# epnet.net
KiCad netlist of a schematic drawn in EAGLE
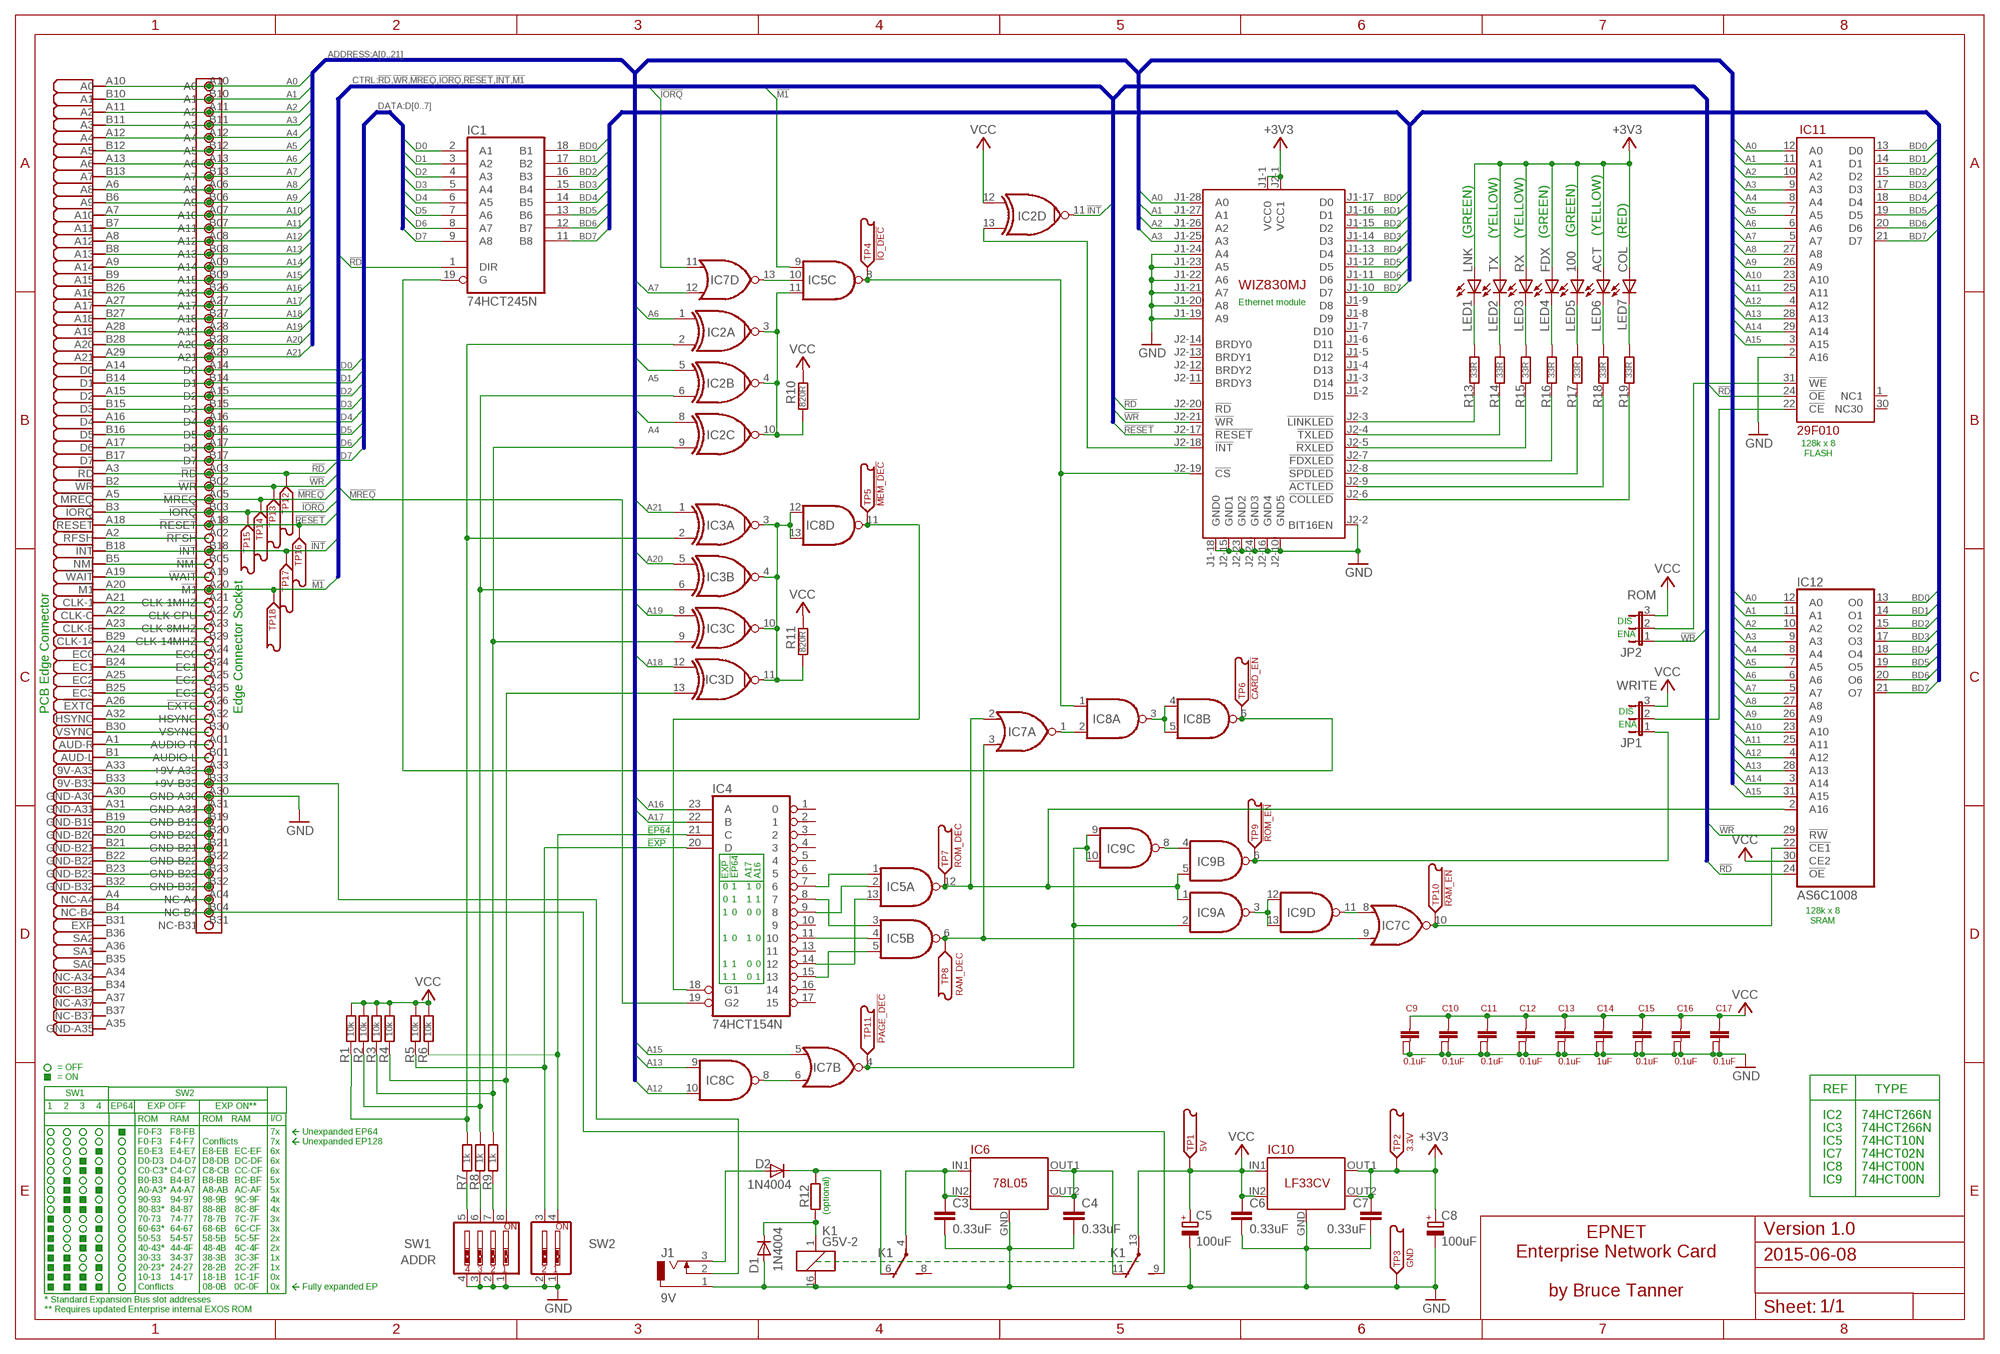
[diagram p0: schematic, sheet 1]

(export (version "E")
  (design (tool "Eeschema 10.0.6"))
  (components
    (comp (ref "C1")
      (value "Edge Connector")
      (footprint "eagle-import:CON-EDGE")
      (libsource (lib "eagle-import") (part "CON-EDGE"))
    )
    (comp (ref "C2")
      (value "CON-EXPANSION")
      (footprint "eagle-import:EXPSOCKET")
      (libsource (lib "eagle-import") (part "CON-EXPANSION"))
    )
    (comp (ref "C3")
      (value "0.33uF")
      (footprint "eagle-import:C050-025X075")
      (libsource (lib "eagle-import") (part "C-EU050-025X075"))
    )
    (comp (ref "C4")
      (value "0.33uF")
      (footprint "eagle-import:C050-025X075")
      (libsource (lib "eagle-import") (part "C-EU050-025X075"))
    )
    (comp (ref "C5")
      (value "100uF")
      (footprint "eagle-import:E2,5-7")
      (libsource (lib "eagle-import") (part "CPOL-EUE2.5-7"))
    )
    (comp (ref "C6")
      (value "0.33uF")
      (footprint "eagle-import:C050-025X075")
      (libsource (lib "eagle-import") (part "C-EU050-025X075"))
    )
    (comp (ref "C7")
      (value "0.33uF")
      (footprint "eagle-import:C050-025X075")
      (libsource (lib "eagle-import") (part "C-EU050-025X075"))
    )
    (comp (ref "C8")
      (value "100uF")
      (footprint "eagle-import:E2,5-7")
      (libsource (lib "eagle-import") (part "CPOL-EUE2.5-7"))
    )
    (comp (ref "C9")
      (value "0.1uF")
      (footprint "eagle-import:CAPACITOR")
      (libsource (lib "eagle-import") (part "CAPACITOR"))
    )
    (comp (ref "C10")
      (value "0.1uF")
      (footprint "eagle-import:CAPACITOR")
      (libsource (lib "eagle-import") (part "CAPACITOR"))
    )
    (comp (ref "C11")
      (value "0.1uF")
      (footprint "eagle-import:CAPACITOR")
      (libsource (lib "eagle-import") (part "CAPACITOR"))
    )
    (comp (ref "C12")
      (value "0.1uF")
      (footprint "eagle-import:CAPACITOR")
      (libsource (lib "eagle-import") (part "CAPACITOR"))
    )
    (comp (ref "C13")
      (value "0.1uF")
      (footprint "eagle-import:CAPACITOR")
      (libsource (lib "eagle-import") (part "CAPACITOR"))
    )
    (comp (ref "C14")
      (value "1uF")
      (footprint "eagle-import:CAPACITOR")
      (libsource (lib "eagle-import") (part "CAPACITOR"))
    )
    (comp (ref "C15")
      (value "0.1uF")
      (footprint "eagle-import:CAPACITOR")
      (libsource (lib "eagle-import") (part "CAPACITOR"))
    )
    (comp (ref "C16")
      (value "0.1uF")
      (footprint "eagle-import:CAPACITOR")
      (libsource (lib "eagle-import") (part "CAPACITOR"))
    )
    (comp (ref "C17")
      (value "0.1uF")
      (footprint "eagle-import:CAPACITOR")
      (libsource (lib "eagle-import") (part "CAPACITOR"))
    )
    (comp (ref "D1")
      (value "1N4004")
      (footprint "eagle-import:DO41-10")
      (libsource (lib "eagle-import") (part "1N4004"))
    )
    (comp (ref "D2")
      (value "1N4004")
      (footprint "eagle-import:DO41-10")
      (libsource (lib "eagle-import") (part "1N4004"))
    )
    (comp (ref "IC1")
      (value "74HCT245N")
      (footprint "eagle-import:DIL20")
      (libsource (lib "eagle-import") (part "74245NLS"))
    )
    (comp (ref "IC2")
      (value "74LS266N")
      (footprint "eagle-import:DIL14")
      (libsource (lib "eagle-import") (part "74266NLS"))
    )
    (comp (ref "IC3")
      (value "74LS266N")
      (footprint "eagle-import:DIL14")
      (libsource (lib "eagle-import") (part "74266NLS"))
    )
    (comp (ref "IC4")
      (value "74HCT154N")
      (footprint "eagle-import:DIL24-6")
      (libsource (lib "eagle-import") (part "74154N"))
    )
    (comp (ref "IC5")
      (value "74AS10N")
      (footprint "eagle-import:DIL14")
      (libsource (lib "eagle-import") (part "7410NAS"))
    )
    (comp (ref "IC6")
      (value "78L05")
      (footprint "eagle-import:REGULATOR")
      (libsource (lib "eagle-import") (part "REGULATOR"))
    )
    (comp (ref "IC7")
      (value "74LS02N")
      (footprint "eagle-import:DIL14")
      (libsource (lib "eagle-import") (part "7402NLS"))
    )
    (comp (ref "IC8")
      (value "74LS00N")
      (footprint "eagle-import:DIL14")
      (libsource (lib "eagle-import") (part "7400NLS"))
    )
    (comp (ref "IC9")
      (value "74LS00N")
      (footprint "eagle-import:DIL14")
      (libsource (lib "eagle-import") (part "7400NLS"))
    )
    (comp (ref "IC10")
      (value "LF33CV")
      (footprint "eagle-import:REGULATOR")
      (libsource (lib "eagle-import") (part "REGULATOR"))
    )
    (comp (ref "IC11")
      (value "29F010")
      (footprint "eagle-import:20F010")
      (libsource (lib "eagle-import") (part "29F010"))
    )
    (comp (ref "IC12")
      (value "AS6C1008")
      (footprint "eagle-import:DIL32")
      (libsource (lib "eagle-import") (part "TC551001CP"))
    )
    (comp (ref "J1")
      (value "9V")
      (footprint "eagle-import:DCJ0202")
      (libsource (lib "eagle-import") (part "DCJ0202"))
    )
    (comp (ref "JP1")
      (value "WRITE")
      (footprint "eagle-import:JP2")
      (libsource (lib "eagle-import") (part "JP2E"))
    )
    (comp (ref "JP2")
      (value "ROM")
      (footprint "eagle-import:JP2")
      (libsource (lib "eagle-import") (part "JP2E"))
    )
    (comp (ref "K1")
      (value "G5V-2")
      (footprint "eagle-import:G5V-2")
      (fields (field (name "MPN") "G5V-2 5DC"))
      (libsource (lib "eagle-import") (part "G5V-2"))
    )
    (comp (ref "LED1")
      (value "LNK")
      (footprint "eagle-import:LED3MM")
      (libsource (lib "eagle-import") (part "LED3MM"))
    )
    (comp (ref "LED2")
      (value "TX")
      (footprint "eagle-import:LED3MM")
      (libsource (lib "eagle-import") (part "LED3MM"))
    )
    (comp (ref "LED3")
      (value "RX")
      (footprint "eagle-import:LED3MM")
      (libsource (lib "eagle-import") (part "LED3MM"))
    )
    (comp (ref "LED4")
      (value "FDX")
      (footprint "eagle-import:LED3MM")
      (libsource (lib "eagle-import") (part "LED3MM"))
    )
    (comp (ref "LED5")
      (value "100")
      (footprint "eagle-import:LED3MM")
      (libsource (lib "eagle-import") (part "LED3MM"))
    )
    (comp (ref "LED6")
      (value "ACT")
      (footprint "eagle-import:LED3MM")
      (libsource (lib "eagle-import") (part "LED3MM"))
    )
    (comp (ref "LED7")
      (value "COL")
      (footprint "eagle-import:LED3MM")
      (libsource (lib "eagle-import") (part "LED3MM"))
    )
    (comp (ref "M1")
      (value "WIZ830MJ")
      (footprint "eagle-import:WIZ830MJ")
      (libsource (lib "eagle-import") (part "WIZ830MJ"))
    )
    (comp (ref "R1")
      (value "10k")
      (footprint "eagle-import:0309_10")
      (libsource (lib "eagle-import") (part "R-EU_0309/10"))
    )
    (comp (ref "R2")
      (value "10k")
      (footprint "eagle-import:0309_10")
      (libsource (lib "eagle-import") (part "R-EU_0309/10"))
    )
    (comp (ref "R3")
      (value "10k")
      (footprint "eagle-import:0309_10")
      (libsource (lib "eagle-import") (part "R-EU_0309/10"))
    )
    (comp (ref "R4")
      (value "10k")
      (footprint "eagle-import:0309_10")
      (libsource (lib "eagle-import") (part "R-EU_0309/10"))
    )
    (comp (ref "R5")
      (value "10k")
      (footprint "eagle-import:0309_10")
      (libsource (lib "eagle-import") (part "R-EU_0309/10"))
    )
    (comp (ref "R6")
      (value "10k")
      (footprint "eagle-import:0309_10")
      (libsource (lib "eagle-import") (part "R-EU_0309/10"))
    )
    (comp (ref "R7")
      (value "1k")
      (footprint "eagle-import:0309_10")
      (libsource (lib "eagle-import") (part "R-EU_0309/10"))
    )
    (comp (ref "R8")
      (value "1k")
      (footprint "eagle-import:0309_10")
      (libsource (lib "eagle-import") (part "R-EU_0309/10"))
    )
    (comp (ref "R9")
      (value "1k")
      (footprint "eagle-import:0309_10")
      (libsource (lib "eagle-import") (part "R-EU_0309/10"))
    )
    (comp (ref "R10")
      (value "820R")
      (footprint "eagle-import:0309_10")
      (libsource (lib "eagle-import") (part "R-EU_0309/10"))
    )
    (comp (ref "R11")
      (value "820R")
      (footprint "eagle-import:0309_10")
      (libsource (lib "eagle-import") (part "R-EU_0309/10"))
    )
    (comp (ref "R12")
      (value "R-EU_0309/10")
      (footprint "eagle-import:0309_10")
      (libsource (lib "eagle-import") (part "R-EU_0309/10"))
    )
    (comp (ref "R13")
      (value "33R")
      (footprint "eagle-import:0309_10")
      (libsource (lib "eagle-import") (part "R-EU_0309/10"))
    )
    (comp (ref "R14")
      (value "33R")
      (footprint "eagle-import:0309_10")
      (libsource (lib "eagle-import") (part "R-EU_0309/10"))
    )
    (comp (ref "R15")
      (value "33R")
      (footprint "eagle-import:0309_10")
      (libsource (lib "eagle-import") (part "R-EU_0309/10"))
    )
    (comp (ref "R16")
      (value "33R")
      (footprint "eagle-import:0309_10")
      (libsource (lib "eagle-import") (part "R-EU_0309/10"))
    )
    (comp (ref "R17")
      (value "33R")
      (footprint "eagle-import:0309_10")
      (libsource (lib "eagle-import") (part "R-EU_0309/10"))
    )
    (comp (ref "R18")
      (value "33R")
      (footprint "eagle-import:0309_10")
      (libsource (lib "eagle-import") (part "R-EU_0309/10"))
    )
    (comp (ref "R19")
      (value "33R")
      (footprint "eagle-import:0309_10")
      (libsource (lib "eagle-import") (part "R-EU_0309/10"))
    )
    (comp (ref "SW1")
      (value "ADDR")
      (footprint "eagle-import:EDG-04")
      (libsource (lib "eagle-import") (part "SW_DIP-4"))
    )
    (comp (ref "SW2")
      (value "SW_DIP-2")
      (footprint "eagle-import:EDG-02")
      (libsource (lib "eagle-import") (part "SW_DIP-2"))
    )
    (comp (ref "TP1")
      (value "5V")
      (footprint "eagle-import:TESTPOINT")
      (libsource (lib "eagle-import") (part "TESTPOINT"))
    )
    (comp (ref "TP2")
      (value "3.3V")
      (footprint "eagle-import:TESTPOINT")
      (libsource (lib "eagle-import") (part "TESTPOINT"))
    )
    (comp (ref "TP3")
      (value "GND")
      (footprint "eagle-import:TESTPOINT")
      (libsource (lib "eagle-import") (part "TESTPOINT"))
    )
    (comp (ref "TP4")
      (value "!IO_DEC")
      (footprint "eagle-import:TESTPOINT")
      (libsource (lib "eagle-import") (part "TESTPOINT"))
    )
    (comp (ref "TP5")
      (value "!MEM_DEC")
      (footprint "eagle-import:TESTPOINT")
      (libsource (lib "eagle-import") (part "TESTPOINT"))
    )
    (comp (ref "TP6")
      (value "!CARD_EN")
      (footprint "eagle-import:TESTPOINT")
      (libsource (lib "eagle-import") (part "TESTPOINT"))
    )
    (comp (ref "TP7")
      (value "ROM_DEC")
      (footprint "eagle-import:TESTPOINT")
      (libsource (lib "eagle-import") (part "TESTPOINT"))
    )
    (comp (ref "TP8")
      (value "RAM_DEC")
      (footprint "eagle-import:TESTPOINT")
      (libsource (lib "eagle-import") (part "TESTPOINT"))
    )
    (comp (ref "TP9")
      (value "!ROM_EN")
      (footprint "eagle-import:TESTPOINT")
      (libsource (lib "eagle-import") (part "TESTPOINT"))
    )
    (comp (ref "TP10")
      (value "!RAM_EN")
      (footprint "eagle-import:TESTPOINT")
      (libsource (lib "eagle-import") (part "TESTPOINT"))
    )
    (comp (ref "TP11")
      (value "!PAGE_DEC")
      (footprint "eagle-import:TESTPOINT")
      (libsource (lib "eagle-import") (part "TESTPOINT"))
    )
    (comp (ref "TP12")
      (value "!RD")
      (footprint "eagle-import:TESTPOINT")
      (libsource (lib "eagle-import") (part "TESTPOINT"))
    )
    (comp (ref "TP13")
      (value "!WR")
      (footprint "eagle-import:TESTPOINT")
      (libsource (lib "eagle-import") (part "TESTPOINT"))
    )
    (comp (ref "TP14")
      (value "!MREQ")
      (footprint "eagle-import:TESTPOINT")
      (libsource (lib "eagle-import") (part "TESTPOINT"))
    )
    (comp (ref "TP15")
      (value "!IORQ")
      (footprint "eagle-import:TESTPOINT")
      (libsource (lib "eagle-import") (part "TESTPOINT"))
    )
    (comp (ref "TP16")
      (value "!RESET")
      (footprint "eagle-import:TESTPOINT")
      (libsource (lib "eagle-import") (part "TESTPOINT"))
    )
    (comp (ref "TP17")
      (value "!INT")
      (footprint "eagle-import:TESTPOINT")
      (libsource (lib "eagle-import") (part "TESTPOINT"))
    )
    (comp (ref "TP18")
      (value "!M1")
      (footprint "eagle-import:TESTPOINT")
      (libsource (lib "eagle-import") (part "TESTPOINT"))
    )
  )
  (nets
    (net (code "32") (name "+3V3") (class "Default")
      (node (ref "C7") (pin "1") (pinfunction "1_1") (pintype "passive"))
      (node (ref "C8") (pin "+") (pinfunction "+_+") (pintype "passive"))
      (node (ref "IC10") (pin "OUT1") (pinfunction "OUT1_OUT1") (pintype "power_in"))
      (node (ref "IC10") (pin "OUT2") (pinfunction "OUT2_OUT2") (pintype "power_in"))
      (node (ref "LED1") (pin "A") (pinfunction "A_A") (pintype "passive"))
      (node (ref "LED2") (pin "A") (pinfunction "A_A") (pintype "passive"))
      (node (ref "LED3") (pin "A") (pinfunction "A_A") (pintype "passive"))
      (node (ref "LED4") (pin "A") (pinfunction "A_A") (pintype "passive"))
      (node (ref "LED5") (pin "A") (pinfunction "A_A") (pintype "passive"))
      (node (ref "LED6") (pin "A") (pinfunction "A_A") (pintype "passive"))
      (node (ref "LED7") (pin "A") (pinfunction "A_A") (pintype "passive"))
      (node (ref "M1") (pin "J1-1") (pinfunction "VCC0_J1-1") (pintype "input"))
      (node (ref "M1") (pin "J2-1") (pinfunction "VCC1_J2-1") (pintype "input"))
      (node (ref "TP2") (pin "P$1") (pinfunction "TESTPOINT_P$1") (pintype "input"))
    )
    (net (code "33") (name "/A0") (class "Default")
      (node (ref "C1") (pin "A10") (pinfunction "A0_A10") (pintype "output"))
      (node (ref "C2") (pin "A10") (pinfunction "A0_A10") (pintype "input"))
      (node (ref "IC11") (pin "12") (pinfunction "A0_12") (pintype "input"))
      (node (ref "IC12") (pin "12") (pinfunction "A0_12") (pintype "input"))
      (node (ref "M1") (pin "J1-28") (pinfunction "A0_J1-28") (pintype "input"))
    )
    (net (code "34") (name "/A1") (class "Default")
      (node (ref "C1") (pin "B10") (pinfunction "A1_B10") (pintype "output"))
      (node (ref "C2") (pin "B10") (pinfunction "A1_B10") (pintype "input"))
      (node (ref "IC11") (pin "11") (pinfunction "A1_11") (pintype "input"))
      (node (ref "IC12") (pin "11") (pinfunction "A1_11") (pintype "input"))
      (node (ref "M1") (pin "J1-27") (pinfunction "A1_J1-27") (pintype "input"))
    )
    (net (code "35") (name "/A2") (class "Default")
      (node (ref "C1") (pin "A11") (pinfunction "A2_A11") (pintype "output"))
      (node (ref "C2") (pin "A11") (pinfunction "A2_A11") (pintype "input"))
      (node (ref "IC11") (pin "10") (pinfunction "A2_10") (pintype "input"))
      (node (ref "IC12") (pin "10") (pinfunction "A2_10") (pintype "input"))
      (node (ref "M1") (pin "J1-26") (pinfunction "A2_J1-26") (pintype "input"))
    )
    (net (code "36") (name "/A3") (class "Default")
      (node (ref "C1") (pin "B11") (pinfunction "A3_B11") (pintype "output"))
      (node (ref "C2") (pin "B11") (pinfunction "A3_B11") (pintype "input"))
      (node (ref "IC11") (pin "9") (pinfunction "A3_9") (pintype "input"))
      (node (ref "IC12") (pin "9") (pinfunction "A3_9") (pintype "input"))
      (node (ref "M1") (pin "J1-25") (pinfunction "A3_J1-25") (pintype "input"))
    )
    (net (code "37") (name "/A4") (class "Default")
      (node (ref "C1") (pin "A12") (pinfunction "A4_A12") (pintype "output"))
      (node (ref "C2") (pin "A12") (pinfunction "A4_A12") (pintype "input"))
      (node (ref "IC11") (pin "8") (pinfunction "A4_8") (pintype "input"))
      (node (ref "IC12") (pin "8") (pinfunction "A4_8") (pintype "input"))
      (node (ref "IC2") (pin "8") (pinfunction "I0_8") (pintype "input"))
    )
    (net (code "38") (name "/A5") (class "Default")
      (node (ref "C1") (pin "B12") (pinfunction "A5_B12") (pintype "output"))
      (node (ref "C2") (pin "B12") (pinfunction "A5_B12") (pintype "input"))
      (node (ref "IC11") (pin "7") (pinfunction "A5_7") (pintype "input"))
      (node (ref "IC12") (pin "7") (pinfunction "A5_7") (pintype "input"))
      (node (ref "IC2") (pin "5") (pinfunction "I0_5") (pintype "input"))
    )
    (net (code "39") (name "/A6") (class "Default")
      (node (ref "C1") (pin "A13") (pinfunction "A6_A13") (pintype "output"))
      (node (ref "C2") (pin "A13") (pinfunction "A6_A13") (pintype "input"))
      (node (ref "IC11") (pin "6") (pinfunction "A6_6") (pintype "input"))
      (node (ref "IC12") (pin "6") (pinfunction "A6_6") (pintype "input"))
      (node (ref "IC2") (pin "1") (pinfunction "I0_1") (pintype "input"))
    )
    (net (code "40") (name "/A7") (class "Default")
      (node (ref "C1") (pin "B13") (pinfunction "A7_B13") (pintype "output"))
      (node (ref "C2") (pin "B13") (pinfunction "A7_B13") (pintype "input"))
      (node (ref "IC11") (pin "5") (pinfunction "A7_5") (pintype "input"))
      (node (ref "IC12") (pin "5") (pinfunction "A7_5") (pintype "input"))
      (node (ref "IC7") (pin "12") (pinfunction "I1_12") (pintype "input"))
    )
    (net (code "41") (name "/A8") (class "Default")
      (node (ref "C1") (pin "A6") (pinfunction "A8_A6") (pintype "output"))
      (node (ref "C2") (pin "A06") (pinfunction "A8_A06") (pintype "input"))
      (node (ref "IC11") (pin "27") (pinfunction "A8_27") (pintype "input"))
      (node (ref "IC12") (pin "27") (pinfunction "A8_27") (pintype "input"))
    )
    (net (code "42") (name "/A9") (class "Default")
      (node (ref "C1") (pin "B6") (pinfunction "A9_B6") (pintype "output"))
      (node (ref "C2") (pin "B06") (pinfunction "A9_B06") (pintype "input"))
      (node (ref "IC11") (pin "26") (pinfunction "A9_26") (pintype "input"))
      (node (ref "IC12") (pin "26") (pinfunction "A9_26") (pintype "input"))
    )
    (net (code "43") (name "/A10") (class "Default")
      (node (ref "C1") (pin "A7") (pinfunction "A10_A7") (pintype "output"))
      (node (ref "C2") (pin "A07") (pinfunction "A10_A07") (pintype "input"))
      (node (ref "IC11") (pin "23") (pinfunction "A10_23") (pintype "input"))
      (node (ref "IC12") (pin "23") (pinfunction "A10_23") (pintype "input"))
    )
    (net (code "44") (name "/A11") (class "Default")
      (node (ref "C1") (pin "B7") (pinfunction "A11_B7") (pintype "output"))
      (node (ref "C2") (pin "B07") (pinfunction "A11_B07") (pintype "input"))
      (node (ref "IC11") (pin "25") (pinfunction "A11_25") (pintype "input"))
      (node (ref "IC12") (pin "25") (pinfunction "A11_25") (pintype "input"))
    )
    (net (code "45") (name "/A12") (class "Default")
      (node (ref "C1") (pin "A8") (pinfunction "A12_A8") (pintype "output"))
      (node (ref "C2") (pin "A08") (pinfunction "A12_A08") (pintype "input"))
      (node (ref "IC11") (pin "4") (pinfunction "A12_4") (pintype "input"))
      (node (ref "IC12") (pin "4") (pinfunction "A12_4") (pintype "input"))
      (node (ref "IC8") (pin "10") (pinfunction "I1_10") (pintype "input"))
    )
    (net (code "46") (name "/A13") (class "Default")
      (node (ref "C1") (pin "B8") (pinfunction "A13_B8") (pintype "output"))
      (node (ref "C2") (pin "B08") (pinfunction "A13_B08") (pintype "input"))
      (node (ref "IC11") (pin "28") (pinfunction "A13_28") (pintype "input"))
      (node (ref "IC12") (pin "28") (pinfunction "A13_28") (pintype "input"))
      (node (ref "IC8") (pin "9") (pinfunction "I0_9") (pintype "input"))
    )
    (net (code "47") (name "/A14") (class "Default")
      (node (ref "C1") (pin "A9") (pinfunction "A14_A9") (pintype "output"))
      (node (ref "C2") (pin "A09") (pinfunction "A14_A09") (pintype "input"))
      (node (ref "IC11") (pin "29") (pinfunction "A14_29") (pintype "input"))
      (node (ref "IC12") (pin "3") (pinfunction "A14_3") (pintype "input"))
    )
    (net (code "48") (name "/A15") (class "Default")
      (node (ref "C1") (pin "B9") (pinfunction "A15_B9") (pintype "output"))
      (node (ref "C2") (pin "B09") (pinfunction "A15_B09") (pintype "input"))
      (node (ref "IC11") (pin "3") (pinfunction "A15_3") (pintype "input"))
      (node (ref "IC12") (pin "31") (pinfunction "A15_31") (pintype "input"))
      (node (ref "IC7") (pin "5") (pinfunction "I0_5") (pintype "input"))
    )
    (net (code "49") (name "/A16") (class "Default")
      (node (ref "C1") (pin "B26") (pinfunction "A16_B26") (pintype "output"))
      (node (ref "C2") (pin "B26") (pinfunction "A16_B26") (pintype "input"))
      (node (ref "IC4") (pin "23") (pinfunction "A_23") (pintype "input"))
    )
    (net (code "50") (name "/A17") (class "Default")
      (node (ref "C1") (pin "A27") (pinfunction "A17_A27") (pintype "output"))
      (node (ref "C2") (pin "A27") (pinfunction "A17_A27") (pintype "input"))
      (node (ref "IC4") (pin "22") (pinfunction "B_22") (pintype "input"))
    )
    (net (code "51") (name "/A18") (class "Default")
      (node (ref "C1") (pin "B27") (pinfunction "A18_B27") (pintype "output"))
      (node (ref "C2") (pin "B27") (pinfunction "A18_B27") (pintype "input"))
      (node (ref "IC3") (pin "12") (pinfunction "I0_12") (pintype "input"))
    )
    (net (code "52") (name "/A19") (class "Default")
      (node (ref "C1") (pin "A28") (pinfunction "A19_A28") (pintype "output"))
      (node (ref "C2") (pin "A28") (pinfunction "A19_A28") (pintype "input"))
      (node (ref "IC3") (pin "8") (pinfunction "I0_8") (pintype "input"))
    )
    (net (code "53") (name "/A20") (class "Default")
      (node (ref "C1") (pin "B28") (pinfunction "A20_B28") (pintype "output"))
      (node (ref "C2") (pin "B28") (pinfunction "A20_B28") (pintype "input"))
      (node (ref "IC3") (pin "5") (pinfunction "I0_5") (pintype "input"))
    )
    (net (code "54") (name "/A21") (class "Default")
      (node (ref "C1") (pin "A29") (pinfunction "A21_A29") (pintype "output"))
      (node (ref "C2") (pin "A29") (pinfunction "A21_A29") (pintype "input"))
      (node (ref "IC3") (pin "1") (pinfunction "I0_1") (pintype "input"))
    )
    (net (code "56") (name "/BD0") (class "Default")
      (node (ref "IC1") (pin "18") (pinfunction "B1_18") (pintype "bidirectional"))
      (node (ref "IC11") (pin "13") (pinfunction "D0_13") (pintype "bidirectional"))
      (node (ref "IC12") (pin "13") (pinfunction "O0_13") (pintype "tri_state"))
      (node (ref "M1") (pin "J1-17") (pinfunction "D0_J1-17") (pintype "bidirectional"))
    )
    (net (code "57") (name "/BD1") (class "Default")
      (node (ref "IC1") (pin "17") (pinfunction "B2_17") (pintype "bidirectional"))
      (node (ref "IC11") (pin "14") (pinfunction "D1_14") (pintype "bidirectional"))
      (node (ref "IC12") (pin "14") (pinfunction "O1_14") (pintype "tri_state"))
      (node (ref "M1") (pin "J1-16") (pinfunction "D1_J1-16") (pintype "bidirectional"))
    )
    (net (code "58") (name "/BD2") (class "Default")
      (node (ref "IC1") (pin "16") (pinfunction "B3_16") (pintype "bidirectional"))
      (node (ref "IC11") (pin "15") (pinfunction "D2_15") (pintype "bidirectional"))
      (node (ref "IC12") (pin "15") (pinfunction "O2_15") (pintype "tri_state"))
      (node (ref "M1") (pin "J1-15") (pinfunction "D2_J1-15") (pintype "bidirectional"))
    )
    (net (code "59") (name "/BD3") (class "Default")
      (node (ref "IC1") (pin "15") (pinfunction "B4_15") (pintype "bidirectional"))
      (node (ref "IC11") (pin "17") (pinfunction "D3_17") (pintype "bidirectional"))
      (node (ref "IC12") (pin "17") (pinfunction "O3_17") (pintype "tri_state"))
      (node (ref "M1") (pin "J1-14") (pinfunction "D3_J1-14") (pintype "bidirectional"))
    )
    (net (code "60") (name "/BD4") (class "Default")
      (node (ref "IC1") (pin "14") (pinfunction "B5_14") (pintype "bidirectional"))
      (node (ref "IC11") (pin "18") (pinfunction "D4_18") (pintype "bidirectional"))
      (node (ref "IC12") (pin "18") (pinfunction "O4_18") (pintype "tri_state"))
      (node (ref "M1") (pin "J1-13") (pinfunction "D4_J1-13") (pintype "bidirectional"))
    )
    (net (code "61") (name "/BD5") (class "Default")
      (node (ref "IC1") (pin "13") (pinfunction "B6_13") (pintype "bidirectional"))
      (node (ref "IC11") (pin "19") (pinfunction "D5_19") (pintype "bidirectional"))
      (node (ref "IC12") (pin "19") (pinfunction "O5_19") (pintype "tri_state"))
      (node (ref "M1") (pin "J1-12") (pinfunction "D5_J1-12") (pintype "bidirectional"))
    )
    (net (code "62") (name "/BD6") (class "Default")
      (node (ref "IC1") (pin "12") (pinfunction "B7_12") (pintype "bidirectional"))
      (node (ref "IC11") (pin "20") (pinfunction "D6_20") (pintype "bidirectional"))
      (node (ref "IC12") (pin "20") (pinfunction "O6_20") (pintype "tri_state"))
      (node (ref "M1") (pin "J1-11") (pinfunction "D6_J1-11") (pintype "bidirectional"))
    )
    (net (code "63") (name "/BD7") (class "Default")
      (node (ref "IC1") (pin "11") (pinfunction "B8_11") (pintype "bidirectional"))
      (node (ref "IC11") (pin "21") (pinfunction "D7_21") (pintype "bidirectional"))
      (node (ref "IC12") (pin "21") (pinfunction "O7_21") (pintype "tri_state"))
      (node (ref "M1") (pin "J1-10") (pinfunction "D7_J1-10") (pintype "bidirectional"))
    )
    (net (code "64") (name "/D0") (class "Default")
      (node (ref "C1") (pin "A14") (pinfunction "D0_A14") (pintype "bidirectional"))
      (node (ref "C2") (pin "A14") (pinfunction "D0_A14") (pintype "bidirectional"))
      (node (ref "IC1") (pin "2") (pinfunction "A1_2") (pintype "bidirectional"))
    )
    (net (code "65") (name "/D1") (class "Default")
      (node (ref "C1") (pin "B14") (pinfunction "D1_B14") (pintype "bidirectional"))
      (node (ref "C2") (pin "B14") (pinfunction "D1_B14") (pintype "bidirectional"))
      (node (ref "IC1") (pin "3") (pinfunction "A2_3") (pintype "bidirectional"))
    )
    (net (code "66") (name "/D2") (class "Default")
      (node (ref "C1") (pin "A15") (pinfunction "D2_A15") (pintype "bidirectional"))
      (node (ref "C2") (pin "A15") (pinfunction "D2_A15") (pintype "bidirectional"))
      (node (ref "IC1") (pin "4") (pinfunction "A3_4") (pintype "bidirectional"))
    )
    (net (code "67") (name "/D3") (class "Default")
      (node (ref "C1") (pin "B15") (pinfunction "D3_B15") (pintype "bidirectional"))
      (node (ref "C2") (pin "B15") (pinfunction "D3_B15") (pintype "bidirectional"))
      (node (ref "IC1") (pin "5") (pinfunction "A4_5") (pintype "bidirectional"))
    )
    (net (code "68") (name "/D4") (class "Default")
      (node (ref "C1") (pin "A16") (pinfunction "D4_A16") (pintype "bidirectional"))
      (node (ref "C2") (pin "A16") (pinfunction "D4_A16") (pintype "bidirectional"))
      (node (ref "IC1") (pin "6") (pinfunction "A5_6") (pintype "bidirectional"))
    )
    (net (code "69") (name "/D5") (class "Default")
      (node (ref "C1") (pin "B16") (pinfunction "D5_B16") (pintype "bidirectional"))
      (node (ref "C2") (pin "B16") (pinfunction "D5_B16") (pintype "bidirectional"))
      (node (ref "IC1") (pin "7") (pinfunction "A6_7") (pintype "bidirectional"))
    )
    (net (code "70") (name "/D6") (class "Default")
      (node (ref "C1") (pin "A17") (pinfunction "D6_A17") (pintype "bidirectional"))
      (node (ref "C2") (pin "A17") (pinfunction "D6_A17") (pintype "bidirectional"))
      (node (ref "IC1") (pin "8") (pinfunction "A7_8") (pintype "bidirectional"))
    )
    (net (code "71") (name "/D7") (class "Default")
      (node (ref "C1") (pin "B17") (pinfunction "D7_B17") (pintype "bidirectional"))
      (node (ref "C2") (pin "B17") (pinfunction "D7_B17") (pintype "bidirectional"))
      (node (ref "IC1") (pin "9") (pinfunction "A8_9") (pintype "bidirectional"))
    )
    (net (code "73") (name "/GND-A35") (class "Default")
      (node (ref "C1") (pin "A35") (pinfunction "GND-A35_A35") (pintype "power_in"))
    )
    (net (code "75") (name "/~{INT}") (class "Default")
      (node (ref "C1") (pin "B18") (pinfunction "~{INT}_B18") (pintype "input"))
      (node (ref "C2") (pin "B18") (pinfunction "~{INT}_B18") (pintype "input"))
      (node (ref "IC2") (pin "11") (pinfunction "O_11") (pintype "open_collector"))
      (node (ref "TP17") (pin "P$1") (pinfunction "TESTPOINT_P$1") (pintype "input"))
    )
    (net (code "76") (name "/~{IORQ}") (class "Default")
      (node (ref "C1") (pin "B3") (pinfunction "~{IORQ}_B3") (pintype "output"))
      (node (ref "C2") (pin "B03") (pinfunction "~{IORQ}_B03") (pintype "input"))
      (node (ref "IC7") (pin "11") (pinfunction "I0_11") (pintype "input"))
      (node (ref "TP15") (pin "P$1") (pinfunction "TESTPOINT_P$1") (pintype "input"))
    )
    (net (code "77") (name "/~{M1}") (class "Default")
      (node (ref "C1") (pin "A20") (pinfunction "~{M1}_A20") (pintype "output"))
      (node (ref "C2") (pin "A20") (pinfunction "~{M1}_A20") (pintype "input"))
      (node (ref "IC5") (pin "9") (pinfunction "I0_9") (pintype "input"))
      (node (ref "TP18") (pin "P$1") (pinfunction "TESTPOINT_P$1") (pintype "input"))
    )
    (net (code "78") (name "/~{MREQ}") (class "Default")
      (node (ref "C1") (pin "A5") (pinfunction "~{MREQ}_A5") (pintype "output"))
      (node (ref "C2") (pin "A05") (pinfunction "~{MREQ}_A05") (pintype "input"))
      (node (ref "IC4") (pin "19") (pinfunction "G2_19") (pintype "input"))
      (node (ref "TP14") (pin "P$1") (pinfunction "TESTPOINT_P$1") (pintype "input"))
    )
    (net (code "79") (name "/~{RD}") (class "Default")
      (node (ref "C1") (pin "A3") (pinfunction "~{RD}_A3") (pintype "output"))
      (node (ref "C2") (pin "A03") (pinfunction "~{RD}_A03") (pintype "input"))
      (node (ref "IC1") (pin "1") (pinfunction "DIR_1") (pintype "input"))
      (node (ref "IC11") (pin "24") (pinfunction "~{OE}_24") (pintype "input"))
      (node (ref "IC12") (pin "24") (pinfunction "~{OE}_24") (pintype "input"))
      (node (ref "M1") (pin "J2-20") (pinfunction "~{RD}_J2-20") (pintype "input"))
      (node (ref "TP12") (pin "P$1") (pinfunction "TESTPOINT_P$1") (pintype "input"))
    )
    (net (code "80") (name "/~{RESET}") (class "Default")
      (node (ref "C1") (pin "A18") (pinfunction "~{RESET}_A18") (pintype "output"))
      (node (ref "C2") (pin "A18") (pinfunction "~{RESET}_A18") (pintype "input"))
      (node (ref "M1") (pin "J2-17") (pinfunction "~{RESET}_J2-17") (pintype "input"))
      (node (ref "TP16") (pin "P$1") (pinfunction "TESTPOINT_P$1") (pintype "input"))
    )
    (net (code "81") (name "/~{WR}") (class "Default")
      (node (ref "C1") (pin "B2") (pinfunction "~{WR}_B2") (pintype "output"))
      (node (ref "C2") (pin "B02") (pinfunction "~{WR}_B02") (pintype "input"))
      (node (ref "IC12") (pin "29") (pinfunction "~{RW}_29") (pintype "input"))
      (node (ref "JP2") (pin "1") (pinfunction "1_1") (pintype "passive"))
      (node (ref "M1") (pin "J2-21") (pinfunction "~{WR}_J2-21") (pintype "input"))
      (node (ref "TP13") (pin "P$1") (pinfunction "TESTPOINT_P$1") (pintype "input"))
    )
    (net (code "82") (name "GND") (class "Default")
      (node (ref "C1") (pin "A30") (pinfunction "GND-A30_A30") (pintype "power_in"))
      (node (ref "C1") (pin "A31") (pinfunction "GND-A31_A31") (pintype "power_in"))
      (node (ref "C1") (pin "B19") (pinfunction "GND-B19_B19") (pintype "power_in"))
      (node (ref "C1") (pin "B20") (pinfunction "GND-B20_B20") (pintype "power_in"))
      (node (ref "C1") (pin "B21") (pinfunction "GND-B21_B21") (pintype "power_in"))
      (node (ref "C1") (pin "B22") (pinfunction "GND-B22_B22") (pintype "power_in"))
      (node (ref "C1") (pin "B23") (pinfunction "GND-B23_B23") (pintype "power_in"))
      (node (ref "C1") (pin "B32") (pinfunction "GND-B32_B32") (pintype "power_in"))
      (node (ref "C10") (pin "P$2") (pinfunction "P$2_P$2") (pintype "input"))
      (node (ref "C10") (pin "P$3") (pinfunction "P$3_P$3") (pintype "bidirectional"))
      (node (ref "C11") (pin "P$2") (pinfunction "P$2_P$2") (pintype "input"))
      (node (ref "C11") (pin "P$3") (pinfunction "P$3_P$3") (pintype "bidirectional"))
      (node (ref "C12") (pin "P$2") (pinfunction "P$2_P$2") (pintype "input"))
      (node (ref "C12") (pin "P$3") (pinfunction "P$3_P$3") (pintype "bidirectional"))
      (node (ref "C13") (pin "P$2") (pinfunction "P$2_P$2") (pintype "input"))
      (node (ref "C13") (pin "P$3") (pinfunction "P$3_P$3") (pintype "bidirectional"))
      (node (ref "C14") (pin "P$2") (pinfunction "P$2_P$2") (pintype "input"))
      (node (ref "C14") (pin "P$3") (pinfunction "P$3_P$3") (pintype "bidirectional"))
      (node (ref "C15") (pin "P$2") (pinfunction "P$2_P$2") (pintype "input"))
      (node (ref "C15") (pin "P$3") (pinfunction "P$3_P$3") (pintype "bidirectional"))
      (node (ref "C16") (pin "P$2") (pinfunction "P$2_P$2") (pintype "input"))
      (node (ref "C16") (pin "P$3") (pinfunction "P$3_P$3") (pintype "bidirectional"))
      (node (ref "C17") (pin "P$2") (pinfunction "P$2_P$2") (pintype "input"))
      (node (ref "C17") (pin "P$3") (pinfunction "P$3_P$3") (pintype "bidirectional"))
      (node (ref "C2") (pin "A30") (pinfunction "GND-A30_A30") (pintype "input"))
      (node (ref "C2") (pin "A31") (pinfunction "GND-A31_A31") (pintype "input"))
      (node (ref "C2") (pin "B19") (pinfunction "GND-B19_B19") (pintype "input"))
      (node (ref "C2") (pin "B20") (pinfunction "GND-B20_B20") (pintype "input"))
      (node (ref "C2") (pin "B21") (pinfunction "GND-B21_B21") (pintype "input"))
      (node (ref "C2") (pin "B22") (pinfunction "GND-B22_B22") (pintype "input"))
      (node (ref "C2") (pin "B23") (pinfunction "GND-B23_B23") (pintype "input"))
      (node (ref "C2") (pin "B32") (pinfunction "GND-B32_B32") (pintype "input"))
      (node (ref "C3") (pin "2") (pinfunction "2_2") (pintype "passive"))
      (node (ref "C4") (pin "2") (pinfunction "2_2") (pintype "passive"))
      (node (ref "C5") (pin "-") (pinfunction "-_-") (pintype "passive"))
      (node (ref "C6") (pin "2") (pinfunction "2_2") (pintype "passive"))
      (node (ref "C7") (pin "2") (pinfunction "2_2") (pintype "passive"))
      (node (ref "C8") (pin "-") (pinfunction "-_-") (pintype "passive"))
      (node (ref "C9") (pin "P$2") (pinfunction "P$2_P$2") (pintype "input"))
      (node (ref "C9") (pin "P$3") (pinfunction "P$3_P$3") (pintype "bidirectional"))
      (node (ref "D1") (pin "A") (pinfunction "A_A") (pintype "passive"))
      (node (ref "IC10") (pin "GND") (pinfunction "GND_GND") (pintype "power_in"))
      (node (ref "IC11") (pin "2") (pinfunction "A16_2") (pintype "input"))
      (node (ref "IC6") (pin "GND") (pinfunction "GND_GND") (pintype "power_in"))
      (node (ref "J1") (pin "1") (pinfunction "1_1") (pintype "passive"))
      (node (ref "K1") (pin "16") (pinfunction "2_16") (pintype "passive"))
      (node (ref "M1") (pin "J1-18") (pinfunction "GND0_J1-18") (pintype "input"))
      (node (ref "M1") (pin "J1-19") (pinfunction "A9_J1-19") (pintype "input"))
      (node (ref "M1") (pin "J1-20") (pinfunction "A8_J1-20") (pintype "input"))
      (node (ref "M1") (pin "J1-21") (pinfunction "A7_J1-21") (pintype "input"))
      (node (ref "M1") (pin "J1-22") (pinfunction "A6_J1-22") (pintype "input"))
      (node (ref "M1") (pin "J1-23") (pinfunction "A5_J1-23") (pintype "input"))
      (node (ref "M1") (pin "J1-24") (pinfunction "A4_J1-24") (pintype "input"))
      (node (ref "M1") (pin "J2-10") (pinfunction "GND5_J2-10") (pintype "bidirectional"))
      (node (ref "M1") (pin "J2-15") (pinfunction "GND1_J2-15") (pintype "input"))
      (node (ref "M1") (pin "J2-16") (pinfunction "GND4_J2-16") (pintype "input"))
      (node (ref "M1") (pin "J2-2") (pinfunction "BIT16EN_J2-2") (pintype "input"))
      (node (ref "M1") (pin "J2-23") (pinfunction "GND2_J2-23") (pintype "input"))
      (node (ref "M1") (pin "J2-24") (pinfunction "GND3_J2-24") (pintype "input"))
      (node (ref "SW1") (pin "1") (pinfunction "1_1") (pintype "passive"))
      (node (ref "SW1") (pin "2") (pinfunction "2_2") (pintype "passive"))
      (node (ref "SW1") (pin "3") (pinfunction "3_3") (pintype "passive"))
      (node (ref "SW1") (pin "4") (pinfunction "4_4") (pintype "passive"))
      (node (ref "SW2") (pin "1") (pinfunction "1_1") (pintype "passive"))
      (node (ref "SW2") (pin "2") (pinfunction "2_2") (pintype "passive"))
      (node (ref "TP3") (pin "P$1") (pinfunction "TESTPOINT_P$1") (pintype "input"))
    )
    (net (code "83") (name "Net-(C1-9V-A33)") (class "Default")
      (node (ref "C1") (pin "A33") (pinfunction "9V-A33_A33") (pintype "power_in"))
      (node (ref "C1") (pin "B33") (pinfunction "9V-B33_B33") (pintype "power_in"))
      (node (ref "C2") (pin "A33") (pinfunction "+9V-A33_A33") (pintype "input"))
      (node (ref "C2") (pin "B33") (pinfunction "+9V-B33_B33") (pintype "input"))
      (node (ref "J1") (pin "2") (pinfunction "2_2") (pintype "passive"))
    )
    (net (code "84") (name "Net-(C1-AUD-L)") (class "Default")
      (node (ref "C1") (pin "B1") (pinfunction "AUD-L_B1") (pintype "output"))
      (node (ref "C2") (pin "B01") (pinfunction "AUDIO-L_B01") (pintype "input"))
    )
    (net (code "85") (name "Net-(C1-AUD-R)") (class "Default")
      (node (ref "C1") (pin "A1") (pinfunction "AUD-R_A1") (pintype "output"))
      (node (ref "C2") (pin "A01") (pinfunction "AUDIO-R_A01") (pintype "input"))
    )
    (net (code "86") (name "Net-(C1-CLK-1)") (class "Default")
      (node (ref "C1") (pin "A21") (pinfunction "CLK-1_A21") (pintype "output"))
      (node (ref "C2") (pin "A21") (pinfunction "CLK-1MHZ_A21") (pintype "input"))
    )
    (net (code "87") (name "Net-(C1-CLK-8)") (class "Default")
      (node (ref "C1") (pin "A23") (pinfunction "CLK-8_A23") (pintype "output"))
      (node (ref "C2") (pin "A23") (pinfunction "CLK-8MHZ_A23") (pintype "input"))
    )
    (net (code "88") (name "Net-(C1-CLK-14)") (class "Default")
      (node (ref "C1") (pin "B29") (pinfunction "CLK-14_B29") (pintype "output"))
      (node (ref "C2") (pin "B29") (pinfunction "CLK-14MHZ_B29") (pintype "input"))
    )
    (net (code "89") (name "Net-(C1-CLK-C)") (class "Default")
      (node (ref "C1") (pin "A22") (pinfunction "CLK-C_A22") (pintype "output"))
      (node (ref "C2") (pin "A22") (pinfunction "CLK-CPU_A22") (pintype "input"))
    )
    (net (code "90") (name "Net-(C1-EC0)") (class "Default")
      (node (ref "C1") (pin "A24") (pinfunction "EC0_A24") (pintype "output"))
      (node (ref "C2") (pin "A24") (pinfunction "EC0_A24") (pintype "input"))
    )
    (net (code "91") (name "Net-(C1-EC1)") (class "Default")
      (node (ref "C1") (pin "B24") (pinfunction "EC1_B24") (pintype "output"))
      (node (ref "C2") (pin "B24") (pinfunction "EC1_B24") (pintype "input"))
    )
    (net (code "92") (name "Net-(C1-EC2)") (class "Default")
      (node (ref "C1") (pin "A25") (pinfunction "EC2_A25") (pintype "output"))
      (node (ref "C2") (pin "A25") (pinfunction "EC2_A25") (pintype "input"))
    )
    (net (code "93") (name "Net-(C1-EC3)") (class "Default")
      (node (ref "C1") (pin "B25") (pinfunction "EC3_B25") (pintype "output"))
      (node (ref "C2") (pin "B25") (pinfunction "EC3_B25") (pintype "input"))
    )
    (net (code "94") (name "Net-(C1-HSYNC)") (class "Default")
      (node (ref "C1") (pin "A32") (pinfunction "HSYNC_A32") (pintype "output"))
      (node (ref "C2") (pin "A32") (pinfunction "HSYNC_A32") (pintype "input"))
    )
    (net (code "95") (name "Net-(C1-NC-A4)") (class "Default")
      (node (ref "C1") (pin "A4") (pinfunction "NC-A4_A4") (pintype "output"))
      (node (ref "C1") (pin "B4") (pinfunction "NC-B4_B4") (pintype "output"))
      (node (ref "C2") (pin "A04") (pinfunction "NC-A4_A04") (pintype "input"))
      (node (ref "C2") (pin "B04") (pinfunction "NC-B4_B04") (pintype "input"))
      (node (ref "K1") (pin "9") (pinfunction "S_9") (pintype "passive"))
    )
    (net (code "96") (name "Net-(C1-VSYNC)") (class "Default")
      (node (ref "C1") (pin "B30") (pinfunction "VSYNC_B30") (pintype "output"))
      (node (ref "C2") (pin "B30") (pinfunction "VSYNC_B30") (pintype "input"))
    )
    (net (code "97") (name "Net-(C1-~{EXTC})") (class "Default")
      (node (ref "C1") (pin "A26") (pinfunction "~{EXTC}_A26") (pintype "output"))
      (node (ref "C2") (pin "A26") (pinfunction "~{EXTC}_A26") (pintype "input"))
    )
    (net (code "98") (name "Net-(C1-~{NMI})") (class "Default")
      (node (ref "C1") (pin "B5") (pinfunction "~{NMI}_B5") (pintype "input"))
      (node (ref "C2") (pin "B05") (pinfunction "~{NMI}_B05") (pintype "input"))
    )
    (net (code "99") (name "Net-(C1-~{RFSH})") (class "Default")
      (node (ref "C1") (pin "A2") (pinfunction "~{RFSH}_A2") (pintype "output"))
      (node (ref "C2") (pin "A02") (pinfunction "~{RFSH}_A02") (pintype "input"))
    )
    (net (code "100") (name "Net-(C1-~{WAIT})") (class "Default")
      (node (ref "C1") (pin "A19") (pinfunction "~{WAIT}_A19") (pintype "input"))
      (node (ref "C2") (pin "A19") (pinfunction "~{WAIT}_A19") (pintype "input"))
    )
    (net (code "101") (name "Net-(D1-PadC)") (class "Default")
      (node (ref "D1") (pin "C") (pinfunction "C_C") (pintype "passive"))
      (node (ref "K1") (pin "1") (pinfunction "1_1") (pintype "passive"))
      (node (ref "R12") (pin "1") (pinfunction "1_1") (pintype "passive"))
    )
    (net (code "102") (name "Net-(D2-PadA)") (class "Default")
      (node (ref "D2") (pin "A") (pinfunction "A_A") (pintype "passive"))
      (node (ref "J1") (pin "3") (pinfunction "3_3") (pintype "passive"))
    )
    (net (code "103") (name "Net-(IC1A-G)") (class "Default")
      (node (ref "IC1") (pin "19") (pinfunction "G_19") (pintype "input"))
      (node (ref "IC8") (pin "6") (pinfunction "O_6") (pintype "output"))
      (node (ref "TP6") (pin "P$1") (pinfunction "TESTPOINT_P$1") (pintype "input"))
    )
    (net (code "104") (name "Net-(IC2A-I1)") (class "Default")
      (node (ref "IC2") (pin "2") (pinfunction "I1_2") (pintype "input"))
      (node (ref "IC3") (pin "2") (pinfunction "I1_2") (pintype "input"))
      (node (ref "R1") (pin "1") (pinfunction "1_1") (pintype "passive"))
      (node (ref "R7") (pin "2") (pinfunction "2_2") (pintype "passive"))
    )
    (net (code "105") (name "Net-(IC2A-O)") (class "Default")
      (node (ref "IC2") (pin "10") (pinfunction "O_10") (pintype "open_collector"))
      (node (ref "IC2") (pin "3") (pinfunction "O_3") (pintype "open_collector"))
      (node (ref "IC2") (pin "4") (pinfunction "O_4") (pintype "open_collector"))
      (node (ref "IC5") (pin "11") (pinfunction "I2_11") (pintype "input"))
      (node (ref "R10") (pin "1") (pinfunction "1_1") (pintype "passive"))
    )
    (net (code "106") (name "Net-(IC2B-I1)") (class "Default")
      (node (ref "IC2") (pin "6") (pinfunction "I1_6") (pintype "input"))
      (node (ref "IC3") (pin "6") (pinfunction "I1_6") (pintype "input"))
      (node (ref "R2") (pin "1") (pinfunction "1_1") (pintype "passive"))
      (node (ref "R8") (pin "2") (pinfunction "2_2") (pintype "passive"))
    )
    (net (code "107") (name "Net-(IC2C-I1)") (class "Default")
      (node (ref "IC2") (pin "9") (pinfunction "I1_9") (pintype "input"))
      (node (ref "IC3") (pin "9") (pinfunction "I1_9") (pintype "input"))
      (node (ref "R3") (pin "1") (pinfunction "1_1") (pintype "passive"))
      (node (ref "R9") (pin "2") (pinfunction "2_2") (pintype "passive"))
    )
    (net (code "108") (name "Net-(IC2D-I1)") (class "Default")
      (node (ref "IC2") (pin "13") (pinfunction "I1_13") (pintype "input"))
      (node (ref "M1") (pin "J2-18") (pinfunction "~{INT}_J2-18") (pintype "output"))
    )
    (net (code "109") (name "Net-(IC3A-O)") (class "Default")
      (node (ref "IC3") (pin "10") (pinfunction "O_10") (pintype "open_collector"))
      (node (ref "IC3") (pin "11") (pinfunction "O_11") (pintype "open_collector"))
      (node (ref "IC3") (pin "3") (pinfunction "O_3") (pintype "open_collector"))
      (node (ref "IC3") (pin "4") (pinfunction "O_4") (pintype "open_collector"))
      (node (ref "IC8") (pin "12") (pinfunction "I0_12") (pintype "input"))
      (node (ref "IC8") (pin "13") (pinfunction "I1_13") (pintype "input"))
      (node (ref "R11") (pin "1") (pinfunction "1_1") (pintype "passive"))
    )
    (net (code "110") (name "Net-(IC3D-I1)") (class "Default")
      (node (ref "IC3") (pin "13") (pinfunction "I1_13") (pintype "input"))
      (node (ref "R4") (pin "1") (pinfunction "1_1") (pintype "passive"))
      (node (ref "SW1") (pin "8") (pinfunction "8_8") (pintype "passive"))
    )
    (net (code "111") (name "Net-(IC4A-6)") (class "Default")
      (node (ref "IC4") (pin "7") (pinfunction "6_7") (pintype "output"))
      (node (ref "IC5") (pin "1") (pinfunction "I0_1") (pintype "input"))
    )
    (net (code "112") (name "Net-(IC4A-7)") (class "Default")
      (node (ref "IC4") (pin "8") (pinfunction "7_8") (pintype "output"))
      (node (ref "IC5") (pin "3") (pinfunction "I0_3") (pintype "input"))
    )
    (net (code "113") (name "Net-(IC4A-8)") (class "Default")
      (node (ref "IC4") (pin "9") (pinfunction "8_9") (pintype "output"))
      (node (ref "IC5") (pin "2") (pinfunction "I1_2") (pintype "input"))
    )
    (net (code "114") (name "Net-(IC4A-10)") (class "Default")
      (node (ref "IC4") (pin "11") (pinfunction "10_11") (pintype "output"))
      (node (ref "IC5") (pin "4") (pinfunction "I1_4") (pintype "input"))
    )
    (net (code "115") (name "Net-(IC4A-12)") (class "Default")
      (node (ref "IC4") (pin "14") (pinfunction "12_14") (pintype "output"))
      (node (ref "IC5") (pin "13") (pinfunction "I2_13") (pintype "input"))
    )
    (net (code "116") (name "Net-(IC4A-13)") (class "Default")
      (node (ref "IC4") (pin "15") (pinfunction "13_15") (pintype "output"))
      (node (ref "IC5") (pin "5") (pinfunction "I2_5") (pintype "input"))
    )
    (net (code "117") (name "Net-(IC4A-C)") (class "Default")
      (node (ref "IC4") (pin "21") (pinfunction "C_21") (pintype "input"))
      (node (ref "R6") (pin "1") (pinfunction "1_1") (pintype "passive"))
      (node (ref "SW2") (pin "4") (pinfunction "4_4") (pintype "passive"))
    )
    (net (code "118") (name "Net-(IC4A-D)") (class "Default")
      (node (ref "IC4") (pin "20") (pinfunction "D_20") (pintype "input"))
      (node (ref "R5") (pin "1") (pinfunction "1_1") (pintype "passive"))
      (node (ref "SW2") (pin "3") (pinfunction "3_3") (pintype "passive"))
    )
    (net (code "119") (name "Net-(IC4A-G1)") (class "Default")
      (node (ref "IC4") (pin "18") (pinfunction "G1_18") (pintype "input"))
      (node (ref "IC8") (pin "11") (pinfunction "O_11") (pintype "output"))
      (node (ref "TP5") (pin "P$1") (pinfunction "TESTPOINT_P$1") (pintype "input"))
    )
    (net (code "120") (name "Net-(IC5B-O)") (class "Default")
      (node (ref "IC5") (pin "6") (pinfunction "O_6") (pintype "output"))
      (node (ref "IC7") (pin "3") (pinfunction "I1_3") (pintype "input"))
      (node (ref "IC7") (pin "9") (pinfunction "I1_9") (pintype "input"))
      (node (ref "TP8") (pin "P$1") (pinfunction "TESTPOINT_P$1") (pintype "input"))
    )
    (net (code "121") (name "Net-(IC5C-I1)") (class "Default")
      (node (ref "IC5") (pin "10") (pinfunction "I1_10") (pintype "input"))
      (node (ref "IC7") (pin "13") (pinfunction "O_13") (pintype "output"))
    )
    (net (code "122") (name "Net-(IC5C-O)") (class "Default")
      (node (ref "IC5") (pin "8") (pinfunction "O_8") (pintype "output"))
      (node (ref "IC8") (pin "1") (pinfunction "I0_1") (pintype "input"))
      (node (ref "M1") (pin "J2-19") (pinfunction "~{CS}_J2-19") (pintype "input"))
      (node (ref "TP4") (pin "P$1") (pinfunction "TESTPOINT_P$1") (pintype "input"))
    )
    (net (code "123") (name "Net-(IC7A-O)") (class "Default")
      (node (ref "IC7") (pin "1") (pinfunction "O_1") (pintype "output"))
      (node (ref "IC8") (pin "2") (pinfunction "I1_2") (pintype "input"))
    )
    (net (code "124") (name "Net-(IC7B-I1)") (class "Default")
      (node (ref "IC7") (pin "6") (pinfunction "I1_6") (pintype "input"))
      (node (ref "IC8") (pin "8") (pinfunction "O_8") (pintype "output"))
    )
    (net (code "125") (name "Net-(IC7B-O)") (class "Default")
      (node (ref "IC7") (pin "4") (pinfunction "O_4") (pintype "output"))
      (node (ref "IC9") (pin "10") (pinfunction "I1_10") (pintype "input"))
      (node (ref "IC9") (pin "2") (pinfunction "I1_2") (pintype "input"))
      (node (ref "IC9") (pin "9") (pinfunction "I0_9") (pintype "input"))
      (node (ref "TP11") (pin "P$1") (pinfunction "TESTPOINT_P$1") (pintype "input"))
    )
    (net (code "126") (name "Net-(IC7C-I0)") (class "Default")
      (node (ref "IC7") (pin "8") (pinfunction "I0_8") (pintype "input"))
      (node (ref "IC9") (pin "11") (pinfunction "O_11") (pintype "output"))
    )
    (net (code "127") (name "Net-(IC8A-O)") (class "Default")
      (node (ref "IC8") (pin "3") (pinfunction "O_3") (pintype "output"))
      (node (ref "IC8") (pin "4") (pinfunction "I0_4") (pintype "input"))
      (node (ref "IC8") (pin "5") (pinfunction "I1_5") (pintype "input"))
    )
    (net (code "128") (name "Net-(IC9A-O)") (class "Default")
      (node (ref "IC9") (pin "12") (pinfunction "I0_12") (pintype "input"))
      (node (ref "IC9") (pin "13") (pinfunction "I1_13") (pintype "input"))
      (node (ref "IC9") (pin "3") (pinfunction "O_3") (pintype "output"))
    )
    (net (code "129") (name "Net-(IC9B-I0)") (class "Default")
      (node (ref "IC9") (pin "4") (pinfunction "I0_4") (pintype "input"))
      (node (ref "IC9") (pin "8") (pinfunction "O_8") (pintype "output"))
    )
    (net (code "130") (name "Net-(IC9B-O)") (class "Default")
      (node (ref "IC9") (pin "6") (pinfunction "O_6") (pintype "output"))
      (node (ref "JP1") (pin "1") (pinfunction "1_1") (pintype "passive"))
      (node (ref "TP9") (pin "P$1") (pinfunction "TESTPOINT_P$1") (pintype "input"))
    )
    (net (code "131") (name "Net-(IC11B-~{CE})") (class "Default")
      (node (ref "IC11") (pin "22") (pinfunction "~{CE}_22") (pintype "input"))
      (node (ref "JP1") (pin "2") (pinfunction "2_2") (pintype "passive"))
    )
    (net (code "132") (name "Net-(IC11B-~{WE})") (class "Default")
      (node (ref "IC11") (pin "31") (pinfunction "~{WE}_31") (pintype "input"))
      (node (ref "JP2") (pin "2") (pinfunction "2_2") (pintype "passive"))
    )
    (net (code "133") (name "Net-(IC12B-A16)") (class "Default")
      (node (ref "IC12") (pin "2") (pinfunction "A16_2") (pintype "input"))
      (node (ref "IC5") (pin "12") (pinfunction "O_12") (pintype "output"))
      (node (ref "IC7") (pin "2") (pinfunction "I0_2") (pintype "input"))
      (node (ref "IC9") (pin "1") (pinfunction "I0_1") (pintype "input"))
      (node (ref "IC9") (pin "5") (pinfunction "I1_5") (pintype "input"))
      (node (ref "TP7") (pin "P$1") (pinfunction "TESTPOINT_P$1") (pintype "input"))
    )
    (net (code "134") (name "Net-(IC12B-~{CE1})") (class "Default")
      (node (ref "IC12") (pin "22") (pinfunction "~{CE1}_22") (pintype "input"))
      (node (ref "IC7") (pin "10") (pinfunction "O_10") (pintype "output"))
      (node (ref "TP10") (pin "P$1") (pinfunction "TESTPOINT_P$1") (pintype "input"))
    )
    (net (code "135") (name "Net-(K1A-O)") (class "Default")
      (node (ref "D2") (pin "C") (pinfunction "C_C") (pintype "passive"))
      (node (ref "K1") (pin "6") (pinfunction "O_6") (pintype "passive"))
      (node (ref "R12") (pin "2") (pinfunction "2_2") (pintype "passive"))
    )
    (net (code "136") (name "Net-(K1A-P)") (class "Default")
      (node (ref "C3") (pin "1") (pinfunction "1_1") (pintype "passive"))
      (node (ref "IC6") (pin "IN1") (pinfunction "IN1_IN1") (pintype "power_in"))
      (node (ref "IC6") (pin "IN2") (pinfunction "IN2_IN2") (pintype "power_in"))
      (node (ref "K1") (pin "4") (pinfunction "P_4") (pintype "passive"))
    )
    (net (code "137") (name "Net-(K1B-O)") (class "Default")
      (node (ref "C4") (pin "1") (pinfunction "1_1") (pintype "passive"))
      (node (ref "IC6") (pin "OUT1") (pinfunction "OUT1_OUT1") (pintype "power_in"))
      (node (ref "IC6") (pin "OUT2") (pinfunction "OUT2_OUT2") (pintype "power_in"))
      (node (ref "K1") (pin "11") (pinfunction "O_11") (pintype "passive"))
    )
    (net (code "138") (name "Net-(LED1-C)") (class "Default")
      (node (ref "LED1") (pin "K") (pinfunction "C_K") (pintype "passive"))
      (node (ref "R13") (pin "2") (pinfunction "2_2") (pintype "passive"))
    )
    (net (code "139") (name "Net-(LED2-C)") (class "Default")
      (node (ref "LED2") (pin "K") (pinfunction "C_K") (pintype "passive"))
      (node (ref "R14") (pin "2") (pinfunction "2_2") (pintype "passive"))
    )
    (net (code "140") (name "Net-(LED3-C)") (class "Default")
      (node (ref "LED3") (pin "K") (pinfunction "C_K") (pintype "passive"))
      (node (ref "R15") (pin "2") (pinfunction "2_2") (pintype "passive"))
    )
    (net (code "141") (name "Net-(LED4-C)") (class "Default")
      (node (ref "LED4") (pin "K") (pinfunction "C_K") (pintype "passive"))
      (node (ref "R16") (pin "2") (pinfunction "2_2") (pintype "passive"))
    )
    (net (code "142") (name "Net-(LED5-C)") (class "Default")
      (node (ref "LED5") (pin "K") (pinfunction "C_K") (pintype "passive"))
      (node (ref "R17") (pin "2") (pinfunction "2_2") (pintype "passive"))
    )
    (net (code "143") (name "Net-(LED6-C)") (class "Default")
      (node (ref "LED6") (pin "K") (pinfunction "C_K") (pintype "passive"))
      (node (ref "R18") (pin "2") (pinfunction "2_2") (pintype "passive"))
    )
    (net (code "144") (name "Net-(LED7-C)") (class "Default")
      (node (ref "LED7") (pin "K") (pinfunction "C_K") (pintype "passive"))
      (node (ref "R19") (pin "2") (pinfunction "2_2") (pintype "passive"))
    )
    (net (code "145") (name "Net-(M1-~{ACTLED})") (class "Default")
      (node (ref "M1") (pin "J2-9") (pinfunction "~{ACTLED}_J2-9") (pintype "output"))
      (node (ref "R18") (pin "1") (pinfunction "1_1") (pintype "passive"))
    )
    (net (code "146") (name "Net-(M1-~{COLLED})") (class "Default")
      (node (ref "M1") (pin "J2-6") (pinfunction "~{COLLED}_J2-6") (pintype "output"))
      (node (ref "R19") (pin "1") (pinfunction "1_1") (pintype "passive"))
    )
    (net (code "147") (name "Net-(M1-~{FDXLED})") (class "Default")
      (node (ref "M1") (pin "J2-7") (pinfunction "~{FDXLED}_J2-7") (pintype "output"))
      (node (ref "R16") (pin "1") (pinfunction "1_1") (pintype "passive"))
    )
    (net (code "148") (name "Net-(M1-~{LINKLED})") (class "Default")
      (node (ref "M1") (pin "J2-3") (pinfunction "~{LINKLED}_J2-3") (pintype "output"))
      (node (ref "R13") (pin "1") (pinfunction "1_1") (pintype "passive"))
    )
    (net (code "149") (name "Net-(M1-~{RXLED})") (class "Default")
      (node (ref "M1") (pin "J2-5") (pinfunction "~{RXLED}_J2-5") (pintype "output"))
      (node (ref "R15") (pin "1") (pinfunction "1_1") (pintype "passive"))
    )
    (net (code "150") (name "Net-(M1-~{SPDLED})") (class "Default")
      (node (ref "M1") (pin "J2-8") (pinfunction "~{SPDLED}_J2-8") (pintype "output"))
      (node (ref "R17") (pin "1") (pinfunction "1_1") (pintype "passive"))
    )
    (net (code "151") (name "Net-(M1-~{TXLED})") (class "Default")
      (node (ref "M1") (pin "J2-4") (pinfunction "~{TXLED}_J2-4") (pintype "output"))
      (node (ref "R14") (pin "1") (pinfunction "1_1") (pintype "passive"))
    )
    (net (code "152") (name "Net-(R7-Pad1)") (class "Default")
      (node (ref "R7") (pin "1") (pinfunction "1_1") (pintype "passive"))
      (node (ref "SW1") (pin "5") (pinfunction "5_5") (pintype "passive"))
    )
    (net (code "153") (name "Net-(R8-Pad1)") (class "Default")
      (node (ref "R8") (pin "1") (pinfunction "1_1") (pintype "passive"))
      (node (ref "SW1") (pin "6") (pinfunction "6_6") (pintype "passive"))
    )
    (net (code "154") (name "Net-(R9-Pad1)") (class "Default")
      (node (ref "R9") (pin "1") (pinfunction "1_1") (pintype "passive"))
      (node (ref "SW1") (pin "7") (pinfunction "7_7") (pintype "passive"))
    )
    (net (code "155") (name "VCC") (class "Default")
      (node (ref "C10") (pin "P$1") (pinfunction "P$1_P$1") (pintype "input"))
      (node (ref "C11") (pin "P$1") (pinfunction "P$1_P$1") (pintype "input"))
      (node (ref "C12") (pin "P$1") (pinfunction "P$1_P$1") (pintype "input"))
      (node (ref "C13") (pin "P$1") (pinfunction "P$1_P$1") (pintype "input"))
      (node (ref "C14") (pin "P$1") (pinfunction "P$1_P$1") (pintype "input"))
      (node (ref "C15") (pin "P$1") (pinfunction "P$1_P$1") (pintype "input"))
      (node (ref "C16") (pin "P$1") (pinfunction "P$1_P$1") (pintype "input"))
      (node (ref "C17") (pin "P$1") (pinfunction "P$1_P$1") (pintype "input"))
      (node (ref "C5") (pin "+") (pinfunction "+_+") (pintype "passive"))
      (node (ref "C6") (pin "1") (pinfunction "1_1") (pintype "passive"))
      (node (ref "C9") (pin "P$1") (pinfunction "P$1_P$1") (pintype "input"))
      (node (ref "IC10") (pin "IN1") (pinfunction "IN1_IN1") (pintype "power_in"))
      (node (ref "IC10") (pin "IN2") (pinfunction "IN2_IN2") (pintype "power_in"))
      (node (ref "IC12") (pin "30") (pinfunction "CE2_30") (pintype "input"))
      (node (ref "IC2") (pin "12") (pinfunction "I0_12") (pintype "input"))
      (node (ref "JP1") (pin "3") (pinfunction "3_3") (pintype "passive"))
      (node (ref "JP2") (pin "3") (pinfunction "3_3") (pintype "passive"))
      (node (ref "K1") (pin "13") (pinfunction "P_13") (pintype "passive"))
      (node (ref "R1") (pin "2") (pinfunction "2_2") (pintype "passive"))
      (node (ref "R10") (pin "2") (pinfunction "2_2") (pintype "passive"))
      (node (ref "R11") (pin "2") (pinfunction "2_2") (pintype "passive"))
      (node (ref "R2") (pin "2") (pinfunction "2_2") (pintype "passive"))
      (node (ref "R3") (pin "2") (pinfunction "2_2") (pintype "passive"))
      (node (ref "R4") (pin "2") (pinfunction "2_2") (pintype "passive"))
      (node (ref "R5") (pin "2") (pinfunction "2_2") (pintype "passive"))
      (node (ref "R6") (pin "2") (pinfunction "2_2") (pintype "passive"))
      (node (ref "TP1") (pin "P$1") (pinfunction "TESTPOINT_P$1") (pintype "input"))
    )
    (net (code "156") (name "unconnected-(C1-NC-A34-PadA34)") (class "Default")
      (node (ref "C1") (pin "A34") (pinfunction "NC-A34_A34") (pintype "no_connect"))
    )
    (net (code "157") (name "unconnected-(C1-NC-A37-PadA37)") (class "Default")
      (node (ref "C1") (pin "A37") (pinfunction "NC-A37_A37") (pintype "no_connect"))
    )
    (net (code "158") (name "unconnected-(C1-NC-B34-PadB34)") (class "Default")
      (node (ref "C1") (pin "B34") (pinfunction "NC-B34_B34") (pintype "no_connect"))
    )
    (net (code "159") (name "unconnected-(C1-NC-B37-PadB37)") (class "Default")
      (node (ref "C1") (pin "B37") (pinfunction "NC-B37_B37") (pintype "no_connect"))
    )
    (net (code "160") (name "unconnected-(C1-SA0-PadB35)") (class "Default")
      (node (ref "C1") (pin "B35") (pinfunction "SA0_B35") (pintype "output"))
    )
    (net (code "161") (name "unconnected-(C1-SA1-PadA36)") (class "Default")
      (node (ref "C1") (pin "A36") (pinfunction "SA1_A36") (pintype "output"))
    )
    (net (code "162") (name "unconnected-(C1-SA2-PadB36)") (class "Default")
      (node (ref "C1") (pin "B36") (pinfunction "SA2_B36") (pintype "output"))
    )
    (net (code "163") (name "unconnected-(C1-~{EXP}-PadB31)") (class "Default")
      (node (ref "C1") (pin "B31") (pinfunction "~{EXP}_B31") (pintype "input"))
    )
    (net (code "164") (name "unconnected-(C2-NC-B31-PadB31)") (class "Default")
      (node (ref "C2") (pin "B31") (pinfunction "NC-B31_B31") (pintype "input"))
    )
    (net (code "165") (name "unconnected-(IC4A-0-Pad1)") (class "Default")
      (node (ref "IC4") (pin "1") (pinfunction "0_1") (pintype "output"))
    )
    (net (code "166") (name "unconnected-(IC4A-1-Pad2)") (class "Default")
      (node (ref "IC4") (pin "2") (pinfunction "1_2") (pintype "output"))
    )
    (net (code "167") (name "unconnected-(IC4A-2-Pad3)") (class "Default")
      (node (ref "IC4") (pin "3") (pinfunction "2_3") (pintype "output"))
    )
    (net (code "168") (name "unconnected-(IC4A-3-Pad4)") (class "Default")
      (node (ref "IC4") (pin "4") (pinfunction "3_4") (pintype "output"))
    )
    (net (code "169") (name "unconnected-(IC4A-4-Pad5)") (class "Default")
      (node (ref "IC4") (pin "5") (pinfunction "4_5") (pintype "output"))
    )
    (net (code "170") (name "unconnected-(IC4A-5-Pad6)") (class "Default")
      (node (ref "IC4") (pin "6") (pinfunction "5_6") (pintype "output"))
    )
    (net (code "171") (name "unconnected-(IC4A-9-Pad10)") (class "Default")
      (node (ref "IC4") (pin "10") (pinfunction "9_10") (pintype "output"))
    )
    (net (code "172") (name "unconnected-(IC4A-11-Pad13)") (class "Default")
      (node (ref "IC4") (pin "13") (pinfunction "11_13") (pintype "output"))
    )
    (net (code "173") (name "unconnected-(IC4A-14-Pad16)") (class "Default")
      (node (ref "IC4") (pin "16") (pinfunction "14_16") (pintype "output"))
    )
    (net (code "174") (name "unconnected-(IC4A-15-Pad17)") (class "Default")
      (node (ref "IC4") (pin "17") (pinfunction "15_17") (pintype "output"))
    )
    (net (code "175") (name "unconnected-(IC11B-NC1-Pad1)") (class "Default")
      (node (ref "IC11") (pin "1") (pinfunction "NC1_1") (pintype "no_connect"))
    )
    (net (code "176") (name "unconnected-(IC11B-NC30-Pad30)") (class "Default")
      (node (ref "IC11") (pin "30") (pinfunction "NC30_30") (pintype "no_connect"))
    )
    (net (code "177") (name "unconnected-(K1A-S-Pad8)") (class "Default")
      (node (ref "K1") (pin "8") (pinfunction "S_8") (pintype "passive"))
    )
    (net (code "178") (name "unconnected-(M1-BRDY0-PadJ2-14)") (class "Default")
      (node (ref "M1") (pin "J2-14") (pinfunction "BRDY0_J2-14") (pintype "output"))
    )
    (net (code "179") (name "unconnected-(M1-BRDY1-PadJ2-13)") (class "Default")
      (node (ref "M1") (pin "J2-13") (pinfunction "BRDY1_J2-13") (pintype "output"))
    )
    (net (code "180") (name "unconnected-(M1-BRDY2-PadJ2-12)") (class "Default")
      (node (ref "M1") (pin "J2-12") (pinfunction "BRDY2_J2-12") (pintype "output"))
    )
    (net (code "181") (name "unconnected-(M1-BRDY3-PadJ2-11)") (class "Default")
      (node (ref "M1") (pin "J2-11") (pinfunction "BRDY3_J2-11") (pintype "output"))
    )
    (net (code "182") (name "unconnected-(M1-D8-PadJ1-9)") (class "Default")
      (node (ref "M1") (pin "J1-9") (pinfunction "D8_J1-9") (pintype "bidirectional"))
    )
    (net (code "183") (name "unconnected-(M1-D9-PadJ1-8)") (class "Default")
      (node (ref "M1") (pin "J1-8") (pinfunction "D9_J1-8") (pintype "bidirectional"))
    )
    (net (code "184") (name "unconnected-(M1-D10-PadJ1-7)") (class "Default")
      (node (ref "M1") (pin "J1-7") (pinfunction "D10_J1-7") (pintype "bidirectional"))
    )
    (net (code "185") (name "unconnected-(M1-D11-PadJ1-6)") (class "Default")
      (node (ref "M1") (pin "J1-6") (pinfunction "D11_J1-6") (pintype "bidirectional"))
    )
    (net (code "186") (name "unconnected-(M1-D12-PadJ1-5)") (class "Default")
      (node (ref "M1") (pin "J1-5") (pinfunction "D12_J1-5") (pintype "bidirectional"))
    )
    (net (code "187") (name "unconnected-(M1-D13-PadJ1-4)") (class "Default")
      (node (ref "M1") (pin "J1-4") (pinfunction "D13_J1-4") (pintype "bidirectional"))
    )
    (net (code "188") (name "unconnected-(M1-D14-PadJ1-3)") (class "Default")
      (node (ref "M1") (pin "J1-3") (pinfunction "D14_J1-3") (pintype "bidirectional"))
    )
    (net (code "189") (name "unconnected-(M1-D15-PadJ1-2)") (class "Default")
      (node (ref "M1") (pin "J1-2") (pinfunction "D15_J1-2") (pintype "bidirectional"))
    )
  )
)
